# dss_smd.net
KiCad netlist of a schematic drawn in EAGLE
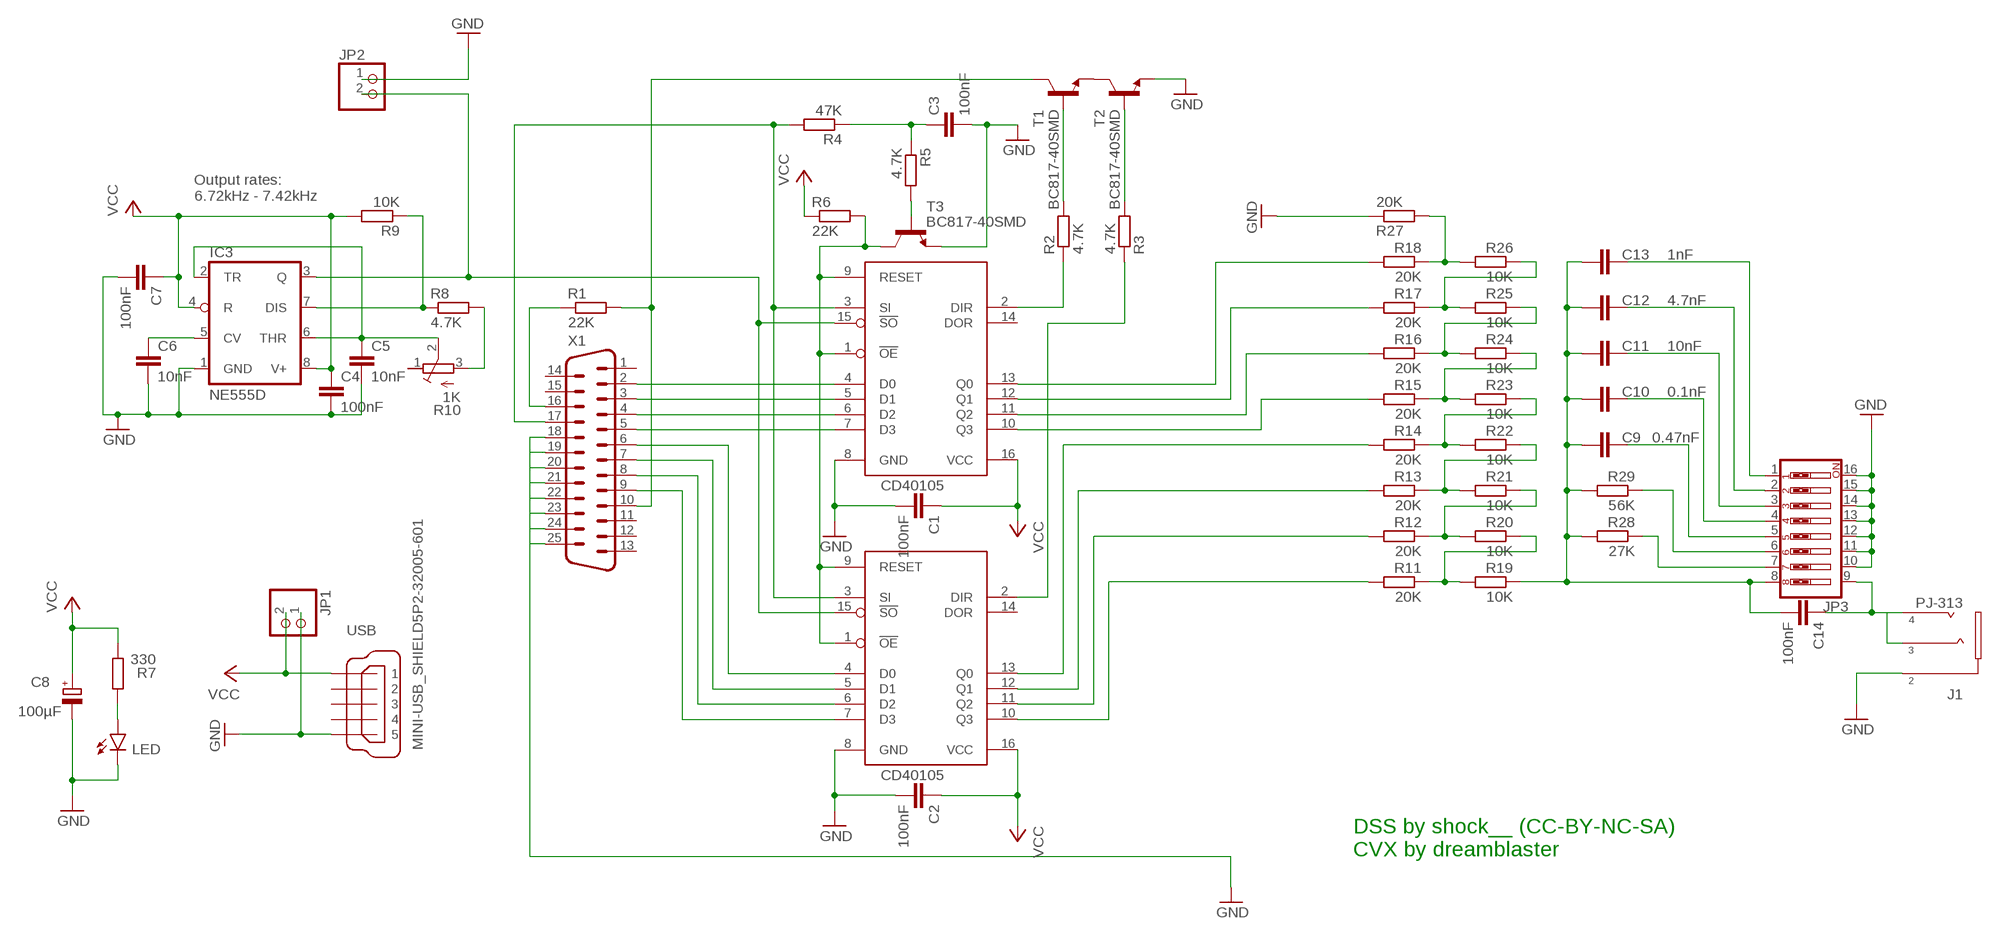
[diagram p0: schematic, sheet 1]

(export (version "E")
  (design (tool "Eeschema 10.0.6"))
  (components
    (comp (ref "C1")
      (value "100nF")
      (footprint "eagle-import:C0805")
      (libsource (lib "eagle-import") (part "C-EUC0805"))
    )
    (comp (ref "C2")
      (value "100nF")
      (footprint "eagle-import:C0805K")
      (libsource (lib "eagle-import") (part "C-EUC0805K"))
    )
    (comp (ref "C3")
      (value "100nF")
      (footprint "eagle-import:C0805K")
      (libsource (lib "eagle-import") (part "C-EUC0805K"))
    )
    (comp (ref "C4")
      (value "100nF")
      (footprint "eagle-import:C0805K")
      (libsource (lib "eagle-import") (part "C-EUC0805K"))
    )
    (comp (ref "C5")
      (value "10nF")
      (footprint "eagle-import:C0805K")
      (libsource (lib "eagle-import") (part "C-EUC0805K"))
    )
    (comp (ref "C6")
      (value "10nF")
      (footprint "eagle-import:C0805K")
      (libsource (lib "eagle-import") (part "C-EUC0805K"))
    )
    (comp (ref "C7")
      (value "100nF")
      (footprint "eagle-import:C0805K")
      (libsource (lib "eagle-import") (part "C-EUC0805K"))
    )
    (comp (ref "C8")
      (value "100µF")
      (footprint "eagle-import:PANASONIC_B")
      (libsource (lib "eagle-import") (part "CPOL-EUB"))
    )
    (comp (ref "C9")
      (value "0.47nF")
      (footprint "eagle-import:C0805K")
      (libsource (lib "eagle-import") (part "C-EUC0805K"))
    )
    (comp (ref "C10")
      (value "0.1nF")
      (footprint "eagle-import:C0805K")
      (libsource (lib "eagle-import") (part "C-EUC0805K"))
    )
    (comp (ref "C11")
      (value "10nF")
      (footprint "eagle-import:C0805K")
      (libsource (lib "eagle-import") (part "C-EUC0805K"))
    )
    (comp (ref "C12")
      (value "4.7nF")
      (footprint "eagle-import:C0805K")
      (libsource (lib "eagle-import") (part "C-EUC0805K"))
    )
    (comp (ref "C13")
      (value "1nF")
      (footprint "eagle-import:C0805K")
      (libsource (lib "eagle-import") (part "C-EUC0805K"))
    )
    (comp (ref "C14")
      (value "100nF")
      (footprint "eagle-import:C0805K")
      (libsource (lib "eagle-import") (part "C-EUC0805K"))
    )
    (comp (ref "IC1")
      (value "CD40105")
      (footprint "eagle-import:DIL16")
      (libsource (lib "eagle-import") (part "CD40105"))
    )
    (comp (ref "IC2")
      (value "CD40105")
      (footprint "eagle-import:DIL16")
      (libsource (lib "eagle-import") (part "CD40105"))
    )
    (comp (ref "IC3")
      (value "NE555D")
      (footprint "eagle-import:SO08")
      (libsource (lib "eagle-import") (part "555DNE"))
    )
    (comp (ref "J1")
      (value "PJ-313")
      (footprint "eagle-import:PJ-313")
      (libsource (lib "eagle-import") (part "PJ-313"))
    )
    (comp (ref "JP1")
      (value "PINHD-1X2")
      (footprint "eagle-import:1X02")
      (libsource (lib "eagle-import") (part "PINHD-1X2"))
    )
    (comp (ref "JP2")
      (value "PINHD-1X2")
      (footprint "eagle-import:1X02")
      (libsource (lib "eagle-import") (part "PINHD-1X2"))
    )
    (comp (ref "JP3")
      (value "SW_DIP-8")
      (footprint "eagle-import:EDG-08")
      (libsource (lib "eagle-import") (part "SW_DIP-8"))
    )
    (comp (ref "LED")
      (value "LEDCHIP-LED0805")
      (footprint "eagle-import:CHIP-LED0805")
      (libsource (lib "eagle-import") (part "LEDCHIP-LED0805"))
    )
    (comp (ref "R1")
      (value "22K")
      (footprint "eagle-import:R0805")
      (libsource (lib "eagle-import") (part "R-EU_R0805"))
    )
    (comp (ref "R2")
      (value "4.7K")
      (footprint "eagle-import:R0805")
      (libsource (lib "eagle-import") (part "R-EU_R0805"))
    )
    (comp (ref "R3")
      (value "4.7K")
      (footprint "eagle-import:R0805")
      (libsource (lib "eagle-import") (part "R-EU_R0805"))
    )
    (comp (ref "R4")
      (value "47K")
      (footprint "eagle-import:R0805")
      (libsource (lib "eagle-import") (part "R-EU_R0805"))
    )
    (comp (ref "R5")
      (value "4.7K")
      (footprint "eagle-import:R0805")
      (libsource (lib "eagle-import") (part "R-EU_R0805"))
    )
    (comp (ref "R6")
      (value "22K")
      (footprint "eagle-import:R0805")
      (libsource (lib "eagle-import") (part "R-EU_R0805"))
    )
    (comp (ref "R7")
      (value "330")
      (footprint "eagle-import:R0805")
      (libsource (lib "eagle-import") (part "R-EU_R0805"))
    )
    (comp (ref "R8")
      (value "4.7K")
      (footprint "eagle-import:R0805")
      (libsource (lib "eagle-import") (part "R-EU_R0805"))
    )
    (comp (ref "R9")
      (value "10K")
      (footprint "eagle-import:R0805")
      (libsource (lib "eagle-import") (part "R-EU_R0805"))
    )
    (comp (ref "R10")
      (value "1K")
      (footprint "eagle-import:RTRIMT93YA")
      (libsource (lib "eagle-import") (part "R-TRIMMT93YA"))
    )
    (comp (ref "R11")
      (value "20K")
      (footprint "eagle-import:R0805")
      (libsource (lib "eagle-import") (part "R-EU_R0805"))
    )
    (comp (ref "R12")
      (value "20K")
      (footprint "eagle-import:R0805")
      (libsource (lib "eagle-import") (part "R-EU_R0805"))
    )
    (comp (ref "R13")
      (value "20K")
      (footprint "eagle-import:R0805")
      (libsource (lib "eagle-import") (part "R-EU_R0805"))
    )
    (comp (ref "R14")
      (value "20K")
      (footprint "eagle-import:R0805")
      (libsource (lib "eagle-import") (part "R-EU_R0805"))
    )
    (comp (ref "R15")
      (value "20K")
      (footprint "eagle-import:R0805")
      (libsource (lib "eagle-import") (part "R-EU_R0805"))
    )
    (comp (ref "R16")
      (value "20K")
      (footprint "eagle-import:R0805")
      (libsource (lib "eagle-import") (part "R-EU_R0805"))
    )
    (comp (ref "R17")
      (value "20K")
      (footprint "eagle-import:R0805")
      (libsource (lib "eagle-import") (part "R-EU_R0805"))
    )
    (comp (ref "R18")
      (value "20K")
      (footprint "eagle-import:R0805")
      (libsource (lib "eagle-import") (part "R-EU_R0805"))
    )
    (comp (ref "R19")
      (value "10K")
      (footprint "eagle-import:R0805")
      (libsource (lib "eagle-import") (part "R-EU_R0805"))
    )
    (comp (ref "R20")
      (value "10K")
      (footprint "eagle-import:R0805")
      (libsource (lib "eagle-import") (part "R-EU_R0805"))
    )
    (comp (ref "R21")
      (value "10K")
      (footprint "eagle-import:R0805")
      (libsource (lib "eagle-import") (part "R-EU_R0805"))
    )
    (comp (ref "R22")
      (value "10K")
      (footprint "eagle-import:R0805")
      (libsource (lib "eagle-import") (part "R-EU_R0805"))
    )
    (comp (ref "R23")
      (value "10K")
      (footprint "eagle-import:R0805")
      (libsource (lib "eagle-import") (part "R-EU_R0805"))
    )
    (comp (ref "R24")
      (value "10K")
      (footprint "eagle-import:R0805")
      (libsource (lib "eagle-import") (part "R-EU_R0805"))
    )
    (comp (ref "R25")
      (value "10K")
      (footprint "eagle-import:R0805")
      (libsource (lib "eagle-import") (part "R-EU_R0805"))
    )
    (comp (ref "R26")
      (value "10K")
      (footprint "eagle-import:R0805")
      (libsource (lib "eagle-import") (part "R-EU_R0805"))
    )
    (comp (ref "R27")
      (value "20K")
      (footprint "eagle-import:R0805")
      (libsource (lib "eagle-import") (part "R-EU_R0805"))
    )
    (comp (ref "R28")
      (value "27K")
      (footprint "eagle-import:R0805")
      (libsource (lib "eagle-import") (part "R-EU_R0805"))
    )
    (comp (ref "R29")
      (value "56K")
      (footprint "eagle-import:R0805")
      (libsource (lib "eagle-import") (part "R-EU_R0805"))
    )
    (comp (ref "T1")
      (value "BC817-40SMD")
      (footprint "eagle-import:SOT23-BEC")
      (libsource (lib "eagle-import") (part "BC817SMD-40"))
    )
    (comp (ref "T2")
      (value "BC817-40SMD")
      (footprint "eagle-import:SOT23-BEC")
      (libsource (lib "eagle-import") (part "BC817SMD-40"))
    )
    (comp (ref "T3")
      (value "BC817-40SMD")
      (footprint "eagle-import:SOT23-BEC")
      (libsource (lib "eagle-import") (part "BC817SMD-40"))
    )
    (comp (ref "USB")
      (value "MINI-USB_SHIELD5P2-32005-601")
      (footprint "eagle-import:32005-601")
      (libsource (lib "eagle-import") (part "MINI-USB_SHIELD5P2-32005-601"))
    )
    (comp (ref "X1")
      (value "HS-LU_M25K")
      (footprint "eagle-import:HS-LU_M25K")
      (libsource (lib "eagle-import") (part "HS-LU_M25K"))
    )
  )
  (nets
    (net (code "1") (name "GND") (class "Default")
      (node (ref "C1") (pin "2") (pinfunction "2_2") (pintype "passive"))
      (node (ref "C2") (pin "2") (pinfunction "2_2") (pintype "passive"))
      (node (ref "C3") (pin "2") (pinfunction "2_2") (pintype "passive"))
      (node (ref "C4") (pin "2") (pinfunction "2_2") (pintype "passive"))
      (node (ref "C5") (pin "2") (pinfunction "2_2") (pintype "passive"))
      (node (ref "C6") (pin "2") (pinfunction "2_2") (pintype "passive"))
      (node (ref "C7") (pin "2") (pinfunction "2_2") (pintype "passive"))
      (node (ref "C8") (pin "-") (pinfunction "-_-") (pintype "passive"))
      (node (ref "IC1") (pin "8") (pinfunction "GND_8") (pintype "power_in"))
      (node (ref "IC2") (pin "8") (pinfunction "GND_8") (pintype "power_in"))
      (node (ref "IC3") (pin "1") (pinfunction "GND_1") (pintype "power_in"))
      (node (ref "J1") (pin "2_1") (pinfunction "2_2_1") (pintype "passive"))
      (node (ref "J1") (pin "2_2") (pinfunction "2_2_2") (pintype "passive"))
      (node (ref "JP1") (pin "1") (pinfunction "1_1") (pintype "passive"))
      (node (ref "JP2") (pin "1") (pinfunction "1_1") (pintype "passive"))
      (node (ref "JP3") (pin "10") (pinfunction "10_10") (pintype "passive"))
      (node (ref "JP3") (pin "11") (pinfunction "11_11") (pintype "passive"))
      (node (ref "JP3") (pin "12") (pinfunction "12_12") (pintype "passive"))
      (node (ref "JP3") (pin "13") (pinfunction "13_13") (pintype "passive"))
      (node (ref "JP3") (pin "14") (pinfunction "14_14") (pintype "passive"))
      (node (ref "JP3") (pin "15") (pinfunction "15_15") (pintype "passive"))
      (node (ref "JP3") (pin "16") (pinfunction "16_16") (pintype "passive"))
      (node (ref "LED") (pin "C") (pinfunction "C_C") (pintype "passive"))
      (node (ref "R27") (pin "1") (pinfunction "1_1") (pintype "passive"))
      (node (ref "T2") (pin "E") (pinfunction "E_E") (pintype "passive"))
      (node (ref "T3") (pin "E") (pinfunction "E_E") (pintype "passive"))
      (node (ref "USB") (pin "5") (pinfunction "5_5") (pintype "passive"))
      (node (ref "X1") (pin "24") (pinfunction "24_24") (pintype "passive"))
      (node (ref "X1") (pin "25") (pinfunction "25_25") (pintype "passive"))
    )
    (net (code "2") (name "Net-(C3-Pad1)") (class "Default")
      (node (ref "C3") (pin "1") (pinfunction "1_1") (pintype "passive"))
      (node (ref "R4") (pin "1") (pinfunction "1_1") (pintype "passive"))
      (node (ref "R5") (pin "1") (pinfunction "1_1") (pintype "passive"))
    )
    (net (code "3") (name "Net-(C9-Pad1)") (class "Default")
      (node (ref "C9") (pin "1") (pinfunction "1_1") (pintype "passive"))
      (node (ref "JP3") (pin "5") (pinfunction "5_5") (pintype "passive"))
    )
    (net (code "4") (name "Net-(C10-Pad1)") (class "Default")
      (node (ref "C10") (pin "1") (pinfunction "1_1") (pintype "passive"))
      (node (ref "JP3") (pin "4") (pinfunction "4_4") (pintype "passive"))
    )
    (net (code "5") (name "Net-(C10-Pad2)") (class "Default")
      (node (ref "C10") (pin "2") (pinfunction "2_2") (pintype "passive"))
      (node (ref "C11") (pin "2") (pinfunction "2_2") (pintype "passive"))
      (node (ref "C12") (pin "2") (pinfunction "2_2") (pintype "passive"))
      (node (ref "C13") (pin "2") (pinfunction "2_2") (pintype "passive"))
      (node (ref "C14") (pin "2") (pinfunction "2_2") (pintype "passive"))
      (node (ref "C9") (pin "2") (pinfunction "2_2") (pintype "passive"))
      (node (ref "JP3") (pin "8") (pinfunction "8_8") (pintype "passive"))
      (node (ref "R19") (pin "1") (pinfunction "1_1") (pintype "passive"))
      (node (ref "R28") (pin "2") (pinfunction "2_2") (pintype "passive"))
      (node (ref "R29") (pin "2") (pinfunction "2_2") (pintype "passive"))
    )
    (net (code "6") (name "Net-(C11-Pad1)") (class "Default")
      (node (ref "C11") (pin "1") (pinfunction "1_1") (pintype "passive"))
      (node (ref "JP3") (pin "3") (pinfunction "3_3") (pintype "passive"))
    )
    (net (code "7") (name "Net-(C12-Pad1)") (class "Default")
      (node (ref "C12") (pin "1") (pinfunction "1_1") (pintype "passive"))
      (node (ref "JP3") (pin "2") (pinfunction "2_2") (pintype "passive"))
    )
    (net (code "8") (name "Net-(C13-Pad1)") (class "Default")
      (node (ref "C13") (pin "1") (pinfunction "1_1") (pintype "passive"))
      (node (ref "JP3") (pin "1") (pinfunction "1_1") (pintype "passive"))
    )
    (net (code "9") (name "Net-(C14-Pad1)") (class "Default")
      (node (ref "C14") (pin "1") (pinfunction "1_1") (pintype "passive"))
      (node (ref "J1") (pin "3") (pinfunction "3_3") (pintype "passive"))
      (node (ref "J1") (pin "4_1") (pinfunction "4_4_1") (pintype "passive"))
      (node (ref "J1") (pin "4_2") (pinfunction "4_4_2") (pintype "passive"))
      (node (ref "JP3") (pin "9") (pinfunction "9_9") (pintype "passive"))
    )
    (net (code "10") (name "Net-(IC1-D0)") (class "Default")
      (node (ref "IC1") (pin "4") (pinfunction "D0_4") (pintype "input"))
      (node (ref "X1") (pin "2") (pinfunction "2_2") (pintype "passive"))
    )
    (net (code "11") (name "Net-(IC1-D1)") (class "Default")
      (node (ref "IC1") (pin "5") (pinfunction "D1_5") (pintype "input"))
      (node (ref "X1") (pin "3") (pinfunction "3_3") (pintype "passive"))
    )
    (net (code "12") (name "Net-(IC1-D2)") (class "Default")
      (node (ref "IC1") (pin "6") (pinfunction "D2_6") (pintype "input"))
      (node (ref "X1") (pin "4") (pinfunction "4_4") (pintype "passive"))
    )
    (net (code "13") (name "Net-(IC1-D3)") (class "Default")
      (node (ref "IC1") (pin "7") (pinfunction "D3_7") (pintype "input"))
      (node (ref "X1") (pin "5") (pinfunction "5_5") (pintype "passive"))
    )
    (net (code "14") (name "Net-(IC1-DIR)") (class "Default")
      (node (ref "IC1") (pin "2") (pinfunction "DIR_2") (pintype "output"))
      (node (ref "R2") (pin "1") (pinfunction "1_1") (pintype "passive"))
    )
    (net (code "15") (name "Net-(IC1-Q0)") (class "Default")
      (node (ref "IC1") (pin "13") (pinfunction "Q0_13") (pintype "output"))
      (node (ref "R18") (pin "2") (pinfunction "2_2") (pintype "passive"))
    )
    (net (code "16") (name "Net-(IC1-Q1)") (class "Default")
      (node (ref "IC1") (pin "12") (pinfunction "Q1_12") (pintype "output"))
      (node (ref "R17") (pin "2") (pinfunction "2_2") (pintype "passive"))
    )
    (net (code "17") (name "Net-(IC1-Q2)") (class "Default")
      (node (ref "IC1") (pin "11") (pinfunction "Q2_11") (pintype "output"))
      (node (ref "R16") (pin "2") (pinfunction "2_2") (pintype "passive"))
    )
    (net (code "18") (name "Net-(IC1-Q3)") (class "Default")
      (node (ref "IC1") (pin "10") (pinfunction "Q3_10") (pintype "output"))
      (node (ref "R15") (pin "2") (pinfunction "2_2") (pintype "passive"))
    )
    (net (code "19") (name "Net-(IC1-RESET)") (class "Default")
      (node (ref "IC1") (pin "1") (pinfunction "~{OE}_1") (pintype "bidirectional"))
      (node (ref "IC1") (pin "9") (pinfunction "RESET_9") (pintype "input"))
      (node (ref "IC2") (pin "1") (pinfunction "~{OE}_1") (pintype "bidirectional"))
      (node (ref "IC2") (pin "9") (pinfunction "RESET_9") (pintype "input"))
      (node (ref "R6") (pin "2") (pinfunction "2_2") (pintype "passive"))
      (node (ref "T3") (pin "C") (pinfunction "C_C") (pintype "passive"))
    )
    (net (code "20") (name "Net-(IC1-SI)") (class "Default")
      (node (ref "IC1") (pin "3") (pinfunction "SI_3") (pintype "input"))
      (node (ref "IC2") (pin "3") (pinfunction "SI_3") (pintype "input"))
      (node (ref "R4") (pin "2") (pinfunction "2_2") (pintype "passive"))
      (node (ref "X1") (pin "17") (pinfunction "17_17") (pintype "passive"))
    )
    (net (code "21") (name "Net-(IC1-~{SO})") (class "Default")
      (node (ref "IC1") (pin "15") (pinfunction "~{SO}_15") (pintype "input"))
      (node (ref "IC2") (pin "15") (pinfunction "~{SO}_15") (pintype "input"))
      (node (ref "IC3") (pin "3") (pinfunction "Q_3") (pintype "output"))
      (node (ref "JP2") (pin "2") (pinfunction "2_2") (pintype "passive"))
    )
    (net (code "22") (name "Net-(IC2-D0)") (class "Default")
      (node (ref "IC2") (pin "4") (pinfunction "D0_4") (pintype "input"))
      (node (ref "X1") (pin "6") (pinfunction "6_6") (pintype "passive"))
    )
    (net (code "23") (name "Net-(IC2-D1)") (class "Default")
      (node (ref "IC2") (pin "5") (pinfunction "D1_5") (pintype "input"))
      (node (ref "X1") (pin "7") (pinfunction "7_7") (pintype "passive"))
    )
    (net (code "24") (name "Net-(IC2-D2)") (class "Default")
      (node (ref "IC2") (pin "6") (pinfunction "D2_6") (pintype "input"))
      (node (ref "X1") (pin "8") (pinfunction "8_8") (pintype "passive"))
    )
    (net (code "25") (name "Net-(IC2-D3)") (class "Default")
      (node (ref "IC2") (pin "7") (pinfunction "D3_7") (pintype "input"))
      (node (ref "X1") (pin "9") (pinfunction "9_9") (pintype "passive"))
    )
    (net (code "26") (name "Net-(IC2-DIR)") (class "Default")
      (node (ref "IC2") (pin "2") (pinfunction "DIR_2") (pintype "output"))
      (node (ref "R3") (pin "1") (pinfunction "1_1") (pintype "passive"))
    )
    (net (code "27") (name "Net-(IC2-Q0)") (class "Default")
      (node (ref "IC2") (pin "13") (pinfunction "Q0_13") (pintype "output"))
      (node (ref "R14") (pin "2") (pinfunction "2_2") (pintype "passive"))
    )
    (net (code "28") (name "Net-(IC2-Q1)") (class "Default")
      (node (ref "IC2") (pin "12") (pinfunction "Q1_12") (pintype "output"))
      (node (ref "R13") (pin "2") (pinfunction "2_2") (pintype "passive"))
    )
    (net (code "29") (name "Net-(IC2-Q2)") (class "Default")
      (node (ref "IC2") (pin "11") (pinfunction "Q2_11") (pintype "output"))
      (node (ref "R12") (pin "2") (pinfunction "2_2") (pintype "passive"))
    )
    (net (code "30") (name "Net-(IC2-Q3)") (class "Default")
      (node (ref "IC2") (pin "10") (pinfunction "Q3_10") (pintype "output"))
      (node (ref "R11") (pin "2") (pinfunction "2_2") (pintype "passive"))
    )
    (net (code "31") (name "Net-(IC3-CV)") (class "Default")
      (node (ref "C6") (pin "1") (pinfunction "1_1") (pintype "passive"))
      (node (ref "IC3") (pin "5") (pinfunction "CV_5") (pintype "input"))
    )
    (net (code "32") (name "Net-(IC3-DIS)") (class "Default")
      (node (ref "IC3") (pin "7") (pinfunction "DIS_7") (pintype "input"))
      (node (ref "R8") (pin "1") (pinfunction "1_1") (pintype "passive"))
      (node (ref "R9") (pin "1") (pinfunction "1_1") (pintype "passive"))
    )
    (net (code "33") (name "Net-(IC3-THR)") (class "Default")
      (node (ref "C5") (pin "1") (pinfunction "1_1") (pintype "passive"))
      (node (ref "IC3") (pin "2") (pinfunction "TR_2") (pintype "input"))
      (node (ref "IC3") (pin "6") (pinfunction "THR_6") (pintype "input"))
      (node (ref "R10") (pin "2") (pinfunction "S_2") (pintype "passive"))
    )
    (net (code "34") (name "Net-(JP3-Pad6)") (class "Default")
      (node (ref "JP3") (pin "6") (pinfunction "6_6") (pintype "passive"))
      (node (ref "R29") (pin "1") (pinfunction "1_1") (pintype "passive"))
    )
    (net (code "35") (name "Net-(JP3-Pad7)") (class "Default")
      (node (ref "JP3") (pin "7") (pinfunction "7_7") (pintype "passive"))
      (node (ref "R28") (pin "1") (pinfunction "1_1") (pintype "passive"))
    )
    (net (code "36") (name "Net-(LED-PadA)") (class "Default")
      (node (ref "LED") (pin "A") (pinfunction "A_A") (pintype "passive"))
      (node (ref "R7") (pin "2") (pinfunction "2_2") (pintype "passive"))
    )
    (net (code "37") (name "Net-(R1-Pad1)") (class "Default")
      (node (ref "R1") (pin "1") (pinfunction "1_1") (pintype "passive"))
      (node (ref "X1") (pin "16") (pinfunction "16_16") (pintype "passive"))
    )
    (net (code "38") (name "Net-(R1-Pad2)") (class "Default")
      (node (ref "R1") (pin "2") (pinfunction "2_2") (pintype "passive"))
      (node (ref "T1") (pin "C") (pinfunction "C_C") (pintype "passive"))
      (node (ref "X1") (pin "10") (pinfunction "10_10") (pintype "passive"))
    )
    (net (code "39") (name "Net-(R2-Pad2)") (class "Default")
      (node (ref "R2") (pin "2") (pinfunction "2_2") (pintype "passive"))
      (node (ref "T1") (pin "B") (pinfunction "B_B") (pintype "passive"))
    )
    (net (code "40") (name "Net-(R3-Pad2)") (class "Default")
      (node (ref "R3") (pin "2") (pinfunction "2_2") (pintype "passive"))
      (node (ref "T2") (pin "B") (pinfunction "B_B") (pintype "passive"))
    )
    (net (code "41") (name "Net-(R5-Pad2)") (class "Default")
      (node (ref "R5") (pin "2") (pinfunction "2_2") (pintype "passive"))
      (node (ref "T3") (pin "B") (pinfunction "B_B") (pintype "passive"))
    )
    (net (code "42") (name "Net-(R10-A)") (class "Default")
      (node (ref "R10") (pin "3") (pinfunction "A_3") (pintype "passive"))
      (node (ref "R8") (pin "2") (pinfunction "2_2") (pintype "passive"))
    )
    (net (code "43") (name "Net-(R11-Pad1)") (class "Default")
      (node (ref "R11") (pin "1") (pinfunction "1_1") (pintype "passive"))
      (node (ref "R19") (pin "2") (pinfunction "2_2") (pintype "passive"))
      (node (ref "R20") (pin "1") (pinfunction "1_1") (pintype "passive"))
    )
    (net (code "44") (name "Net-(R12-Pad1)") (class "Default")
      (node (ref "R12") (pin "1") (pinfunction "1_1") (pintype "passive"))
      (node (ref "R20") (pin "2") (pinfunction "2_2") (pintype "passive"))
      (node (ref "R21") (pin "1") (pinfunction "1_1") (pintype "passive"))
    )
    (net (code "45") (name "Net-(R13-Pad1)") (class "Default")
      (node (ref "R13") (pin "1") (pinfunction "1_1") (pintype "passive"))
      (node (ref "R21") (pin "2") (pinfunction "2_2") (pintype "passive"))
      (node (ref "R22") (pin "1") (pinfunction "1_1") (pintype "passive"))
    )
    (net (code "46") (name "Net-(R14-Pad1)") (class "Default")
      (node (ref "R14") (pin "1") (pinfunction "1_1") (pintype "passive"))
      (node (ref "R22") (pin "2") (pinfunction "2_2") (pintype "passive"))
      (node (ref "R23") (pin "1") (pinfunction "1_1") (pintype "passive"))
    )
    (net (code "47") (name "Net-(R15-Pad1)") (class "Default")
      (node (ref "R15") (pin "1") (pinfunction "1_1") (pintype "passive"))
      (node (ref "R23") (pin "2") (pinfunction "2_2") (pintype "passive"))
      (node (ref "R24") (pin "1") (pinfunction "1_1") (pintype "passive"))
    )
    (net (code "48") (name "Net-(R16-Pad1)") (class "Default")
      (node (ref "R16") (pin "1") (pinfunction "1_1") (pintype "passive"))
      (node (ref "R24") (pin "2") (pinfunction "2_2") (pintype "passive"))
      (node (ref "R25") (pin "1") (pinfunction "1_1") (pintype "passive"))
    )
    (net (code "49") (name "Net-(R17-Pad1)") (class "Default")
      (node (ref "R17") (pin "1") (pinfunction "1_1") (pintype "passive"))
      (node (ref "R25") (pin "2") (pinfunction "2_2") (pintype "passive"))
      (node (ref "R26") (pin "1") (pinfunction "1_1") (pintype "passive"))
    )
    (net (code "50") (name "Net-(R18-Pad1)") (class "Default")
      (node (ref "R18") (pin "1") (pinfunction "1_1") (pintype "passive"))
      (node (ref "R26") (pin "2") (pinfunction "2_2") (pintype "passive"))
      (node (ref "R27") (pin "2") (pinfunction "2_2") (pintype "passive"))
    )
    (net (code "51") (name "Net-(T1-PadE)") (class "Default")
      (node (ref "T1") (pin "E") (pinfunction "E_E") (pintype "passive"))
      (node (ref "T2") (pin "C") (pinfunction "C_C") (pintype "passive"))
    )
    (net (code "52") (name "VCC") (class "Default")
      (node (ref "C1") (pin "1") (pinfunction "1_1") (pintype "passive"))
      (node (ref "C2") (pin "1") (pinfunction "1_1") (pintype "passive"))
      (node (ref "C4") (pin "1") (pinfunction "1_1") (pintype "passive"))
      (node (ref "C7") (pin "1") (pinfunction "1_1") (pintype "passive"))
      (node (ref "C8") (pin "+") (pinfunction "+_+") (pintype "passive"))
      (node (ref "IC1") (pin "16") (pinfunction "VCC_16") (pintype "power_in"))
      (node (ref "IC2") (pin "16") (pinfunction "VCC_16") (pintype "power_in"))
      (node (ref "IC3") (pin "4") (pinfunction "R_4") (pintype "input"))
      (node (ref "IC3") (pin "8") (pinfunction "V+_8") (pintype "power_in"))
      (node (ref "JP1") (pin "2") (pinfunction "2_2") (pintype "passive"))
      (node (ref "R6") (pin "1") (pinfunction "1_1") (pintype "passive"))
      (node (ref "R7") (pin "1") (pinfunction "1_1") (pintype "passive"))
      (node (ref "R9") (pin "2") (pinfunction "2_2") (pintype "passive"))
      (node (ref "USB") (pin "1") (pinfunction "1_1") (pintype "passive"))
    )
    (net (code "53") (name "unconnected-(IC1-DOR-Pad14)") (class "Default")
      (node (ref "IC1") (pin "14") (pinfunction "DOR_14") (pintype "input"))
    )
    (net (code "54") (name "unconnected-(IC2-DOR-Pad14)") (class "Default")
      (node (ref "IC2") (pin "14") (pinfunction "DOR_14") (pintype "input"))
    )
    (net (code "55") (name "unconnected-(R10-E-Pad1)") (class "Default")
      (node (ref "R10") (pin "1") (pinfunction "E_1") (pintype "passive"))
    )
    (net (code "56") (name "unconnected-(USB-Pad2)") (class "Default")
      (node (ref "USB") (pin "2") (pinfunction "2_2") (pintype "passive"))
    )
    (net (code "57") (name "unconnected-(USB-Pad3)") (class "Default")
      (node (ref "USB") (pin "3") (pinfunction "3_3") (pintype "passive"))
    )
    (net (code "58") (name "unconnected-(USB-Pad4)") (class "Default")
      (node (ref "USB") (pin "4") (pinfunction "4_4") (pintype "passive"))
    )
    (net (code "59") (name "unconnected-(X1-Pad1)") (class "Default")
      (node (ref "X1") (pin "1") (pinfunction "1_1") (pintype "passive"))
    )
    (net (code "60") (name "unconnected-(X1-Pad11)") (class "Default")
      (node (ref "X1") (pin "11") (pinfunction "11_11") (pintype "passive"))
    )
    (net (code "61") (name "unconnected-(X1-Pad12)") (class "Default")
      (node (ref "X1") (pin "12") (pinfunction "12_12") (pintype "passive"))
    )
    (net (code "62") (name "unconnected-(X1-Pad13)") (class "Default")
      (node (ref "X1") (pin "13") (pinfunction "13_13") (pintype "passive"))
    )
    (net (code "63") (name "unconnected-(X1-Pad14)") (class "Default")
      (node (ref "X1") (pin "14") (pinfunction "14_14") (pintype "passive"))
    )
    (net (code "64") (name "unconnected-(X1-Pad15)") (class "Default")
      (node (ref "X1") (pin "15") (pinfunction "15_15") (pintype "passive"))
    )
    (net (code "65") (name "unconnected-(X1-Pad18)") (class "Default")
      (node (ref "X1") (pin "18") (pinfunction "18_18") (pintype "passive"))
    )
    (net (code "66") (name "unconnected-(X1-Pad19)") (class "Default")
      (node (ref "X1") (pin "19") (pinfunction "19_19") (pintype "passive"))
    )
    (net (code "67") (name "unconnected-(X1-Pad20)") (class "Default")
      (node (ref "X1") (pin "20") (pinfunction "20_20") (pintype "passive"))
    )
    (net (code "68") (name "unconnected-(X1-Pad21)") (class "Default")
      (node (ref "X1") (pin "21") (pinfunction "21_21") (pintype "passive"))
    )
    (net (code "69") (name "unconnected-(X1-Pad22)") (class "Default")
      (node (ref "X1") (pin "22") (pinfunction "22_22") (pintype "passive"))
    )
    (net (code "70") (name "unconnected-(X1-Pad23)") (class "Default")
      (node (ref "X1") (pin "23") (pinfunction "23_23") (pintype "passive"))
    )
  )
)
